# LNOccupancy.net
KiCad netlist of a schematic drawn in EAGLE
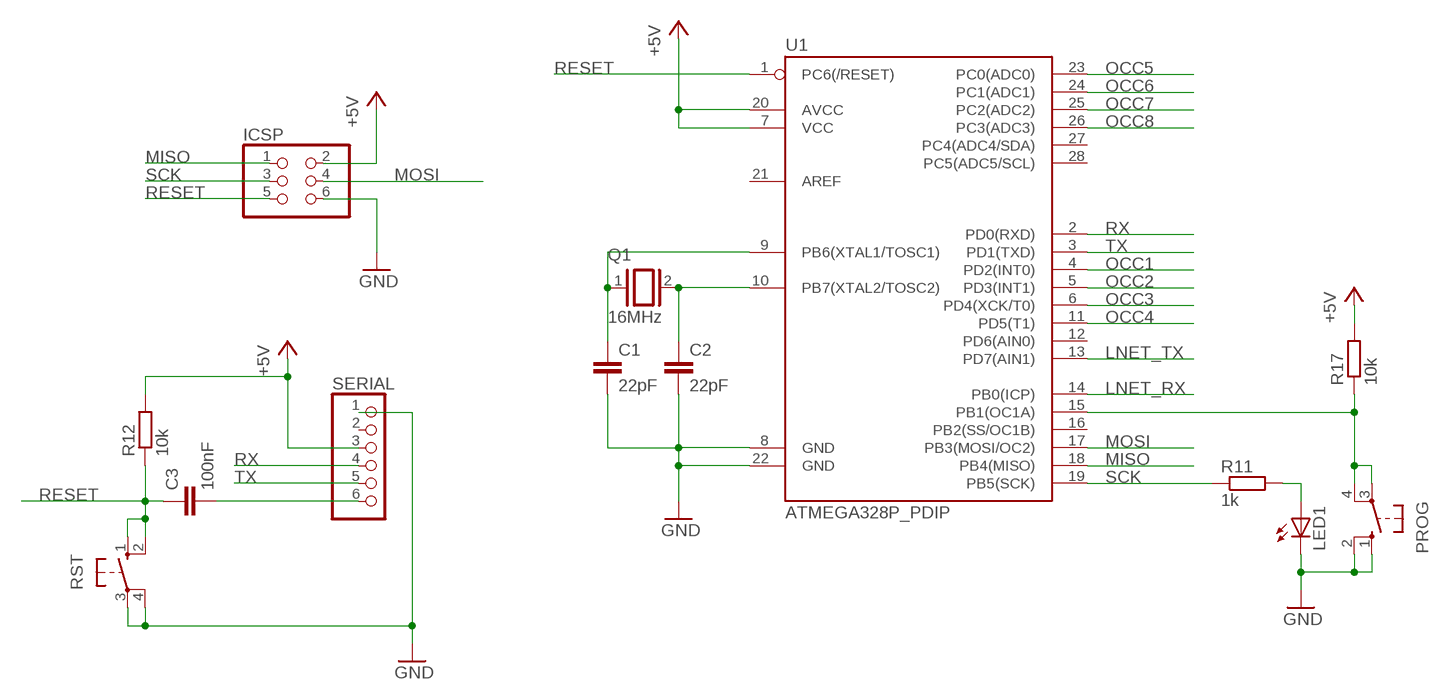
[diagram p0: schematic, sheet 1]
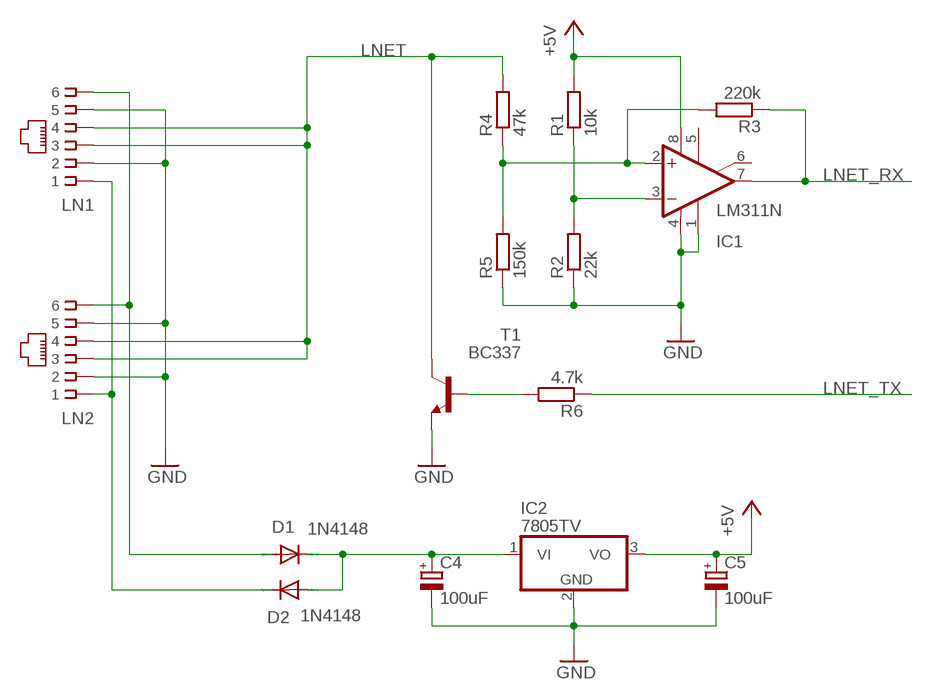
[diagram p1: schematic, sheet 2]
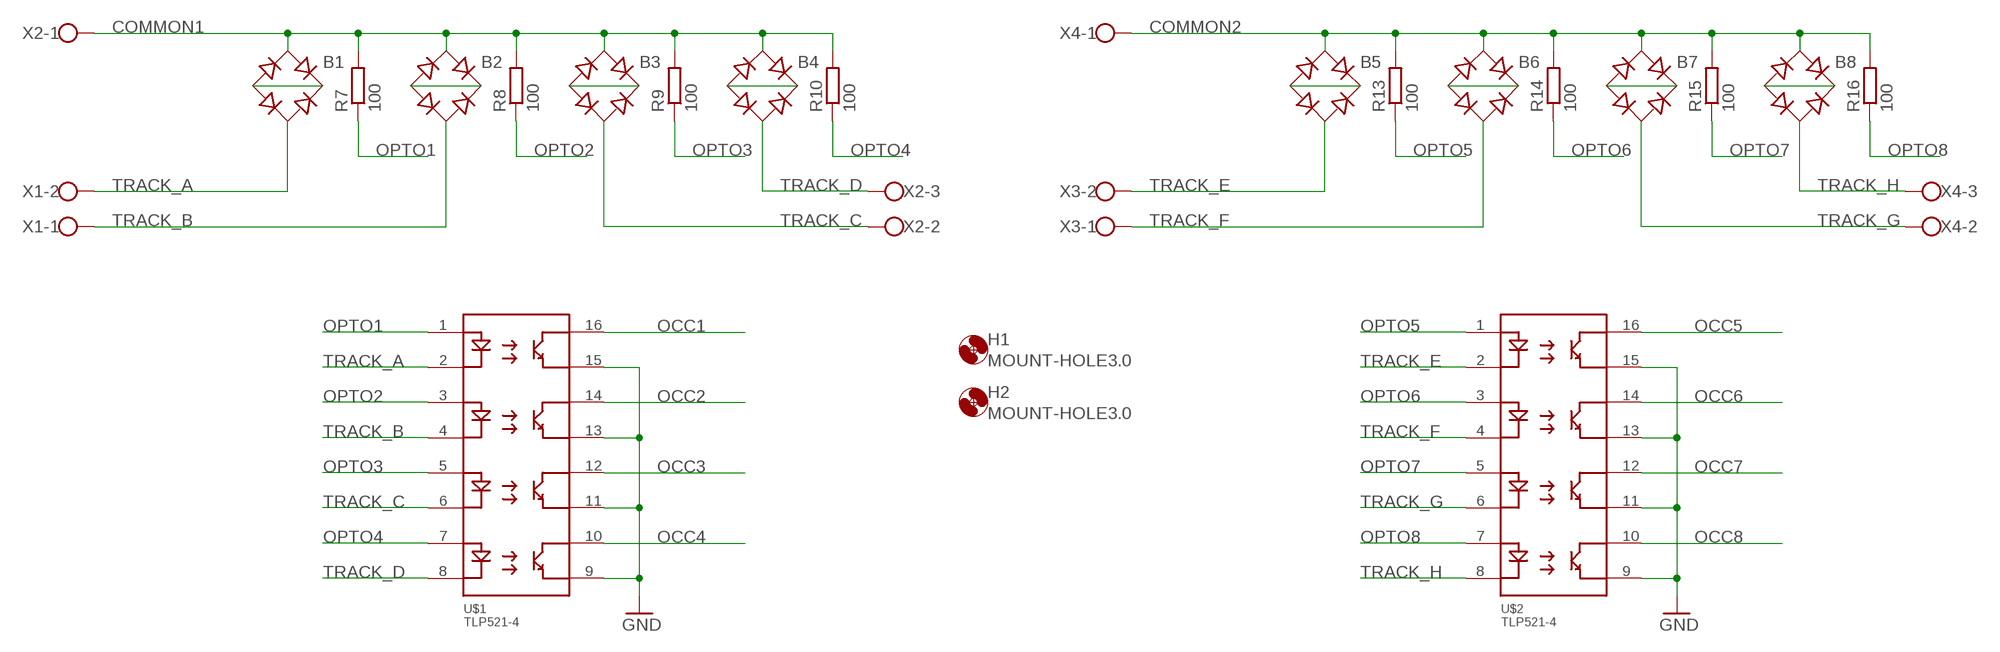
[diagram p2: schematic, sheet 3]

(export (version "E")
  (design (tool "Eeschema 10.0.6"))
  (components
    (comp (ref "C1")
      (value "22pF")
      (footprint "eagle-import:C025-025X050")
      (libsource (lib "eagle-import") (part "C-EU025-025X050"))
    )
    (comp (ref "C2")
      (value "22pF")
      (footprint "eagle-import:C025-025X050")
      (libsource (lib "eagle-import") (part "C-EU025-025X050"))
    )
    (comp (ref "C3")
      (value "100nF")
      (footprint "eagle-import:C050-025X075")
      (libsource (lib "eagle-import") (part "C-EU050-025X075"))
    )
    (comp (ref "ICSP")
      (value "PINHD-2X3")
      (footprint "eagle-import:2X03")
      (libsource (lib "eagle-import") (part "PINHD-2X3"))
    )
    (comp (ref "LED1")
      (value "LED3MM")
      (footprint "eagle-import:LED3MM")
      (libsource (lib "eagle-import") (part "LED3MM"))
    )
    (comp (ref "PROG")
      (value "10-XX")
      (footprint "eagle-import:B3F-10XX")
      (fields (field (name "MPN") "B3F-1000"))
      (libsource (lib "eagle-import") (part "10-XX"))
    )
    (comp (ref "Q1")
      (value "16MHz")
      (footprint "eagle-import:QS")
      (libsource (lib "eagle-import") (part "XTAL/S"))
    )
    (comp (ref "R11")
      (value "1k")
      (footprint "eagle-import:0207_2V")
      (libsource (lib "eagle-import") (part "R-EU_0207/2V"))
    )
    (comp (ref "R12")
      (value "10k")
      (footprint "eagle-import:0207_2V")
      (libsource (lib "eagle-import") (part "R-EU_0207/2V"))
    )
    (comp (ref "R17")
      (value "10k")
      (footprint "eagle-import:0207_2V")
      (libsource (lib "eagle-import") (part "R-EU_0207/2V"))
    )
    (comp (ref "RST")
      (value "10-XX")
      (footprint "eagle-import:B3F-10XX")
      (fields (field (name "MPN") "B3F-1000"))
      (libsource (lib "eagle-import") (part "10-XX"))
    )
    (comp (ref "SERIAL")
      (value "PINHD-1X6")
      (footprint "eagle-import:1X06")
      (libsource (lib "eagle-import") (part "PINHD-1X6"))
    )
    (comp (ref "U1")
      (value "ATMEGA328P_PDIP")
      (footprint "eagle-import:DIL28-3")
      (libsource (lib "eagle-import") (part "ATMEGA328P_PDIP"))
    )
    (comp (ref "B1")
      (value "RB1A")
      (footprint "eagle-import:RB1A")
      (libsource (lib "eagle-import") (part "RB1A"))
    )
    (comp (ref "B2")
      (value "RB1A")
      (footprint "eagle-import:RB1A")
      (libsource (lib "eagle-import") (part "RB1A"))
    )
    (comp (ref "B3")
      (value "RB1A")
      (footprint "eagle-import:RB1A")
      (libsource (lib "eagle-import") (part "RB1A"))
    )
    (comp (ref "B4")
      (value "RB1A")
      (footprint "eagle-import:RB1A")
      (libsource (lib "eagle-import") (part "RB1A"))
    )
    (comp (ref "B5")
      (value "RB1A")
      (footprint "eagle-import:RB1A")
      (libsource (lib "eagle-import") (part "RB1A"))
    )
    (comp (ref "B6")
      (value "RB1A")
      (footprint "eagle-import:RB1A")
      (libsource (lib "eagle-import") (part "RB1A"))
    )
    (comp (ref "B7")
      (value "RB1A")
      (footprint "eagle-import:RB1A")
      (libsource (lib "eagle-import") (part "RB1A"))
    )
    (comp (ref "B8")
      (value "RB1A")
      (footprint "eagle-import:RB1A")
      (libsource (lib "eagle-import") (part "RB1A"))
    )
    (comp (ref "H1")
      (value "MOUNT-HOLE3.0")
      (footprint "eagle-import:3,0")
      (libsource (lib "eagle-import") (part "MOUNT-HOLE3.0"))
    )
    (comp (ref "H2")
      (value "MOUNT-HOLE3.0")
      (footprint "eagle-import:3,0")
      (libsource (lib "eagle-import") (part "MOUNT-HOLE3.0"))
    )
    (comp (ref "R7")
      (value "100")
      (footprint "eagle-import:0207_2V")
      (libsource (lib "eagle-import") (part "R-EU_0207/2V"))
    )
    (comp (ref "R8")
      (value "100")
      (footprint "eagle-import:0207_2V")
      (libsource (lib "eagle-import") (part "R-EU_0207/2V"))
    )
    (comp (ref "R9")
      (value "100")
      (footprint "eagle-import:0207_2V")
      (libsource (lib "eagle-import") (part "R-EU_0207/2V"))
    )
    (comp (ref "R10")
      (value "100")
      (footprint "eagle-import:0207_2V")
      (libsource (lib "eagle-import") (part "R-EU_0207/2V"))
    )
    (comp (ref "R13")
      (value "100")
      (footprint "eagle-import:0207_2V")
      (libsource (lib "eagle-import") (part "R-EU_0207/2V"))
    )
    (comp (ref "R14")
      (value "100")
      (footprint "eagle-import:0207_2V")
      (libsource (lib "eagle-import") (part "R-EU_0207/2V"))
    )
    (comp (ref "R15")
      (value "100")
      (footprint "eagle-import:0207_2V")
      (libsource (lib "eagle-import") (part "R-EU_0207/2V"))
    )
    (comp (ref "R16")
      (value "100")
      (footprint "eagle-import:0207_2V")
      (libsource (lib "eagle-import") (part "R-EU_0207/2V"))
    )
    (comp (ref "U$1")
      (value "TLP521-4")
      (footprint "eagle-import:DIL16")
      (libsource (lib "eagle-import") (part "TLP521-4"))
    )
    (comp (ref "U$2")
      (value "TLP521-4")
      (footprint "eagle-import:DIL16")
      (libsource (lib "eagle-import") (part "TLP521-4"))
    )
    (comp (ref "X1")
      (value "W237-102")
      (footprint "eagle-import:W237-102")
      (fields (field (name "MPN") "237-102"))
      (libsource (lib "eagle-import") (part "W237-102"))
    )
    (comp (ref "X2")
      (value "W237-103")
      (footprint "eagle-import:W237-103")
      (fields (field (name "MPN") "237-103"))
      (libsource (lib "eagle-import") (part "W237-103"))
    )
    (comp (ref "X3")
      (value "W237-102")
      (footprint "eagle-import:W237-102")
      (fields (field (name "MPN") "237-102"))
      (libsource (lib "eagle-import") (part "W237-102"))
    )
    (comp (ref "X4")
      (value "W237-103")
      (footprint "eagle-import:W237-103")
      (fields (field (name "MPN") "237-103"))
      (libsource (lib "eagle-import") (part "W237-103"))
    )
    (comp (ref "C4")
      (value "100uF")
      (footprint "eagle-import:E2,5-6")
      (libsource (lib "eagle-import") (part "CPOL-EUE2.5-6"))
    )
    (comp (ref "C5")
      (value "100uF")
      (footprint "eagle-import:E2,5-6")
      (libsource (lib "eagle-import") (part "CPOL-EUE2.5-6"))
    )
    (comp (ref "D1")
      (value "1N4148")
      (footprint "eagle-import:DO35-10")
      (libsource (lib "eagle-import") (part "1N4148DO35-10"))
    )
    (comp (ref "D2")
      (value "1N4148")
      (footprint "eagle-import:DO35-10")
      (libsource (lib "eagle-import") (part "1N4148DO35-10"))
    )
    (comp (ref "IC1")
      (value "LM311N")
      (footprint "eagle-import:DIL08")
      (libsource (lib "eagle-import") (part "LM311N"))
    )
    (comp (ref "IC2")
      (value "7805TV")
      (footprint "eagle-import:TO220V")
      (libsource (lib "eagle-import") (part "78TV05"))
    )
    (comp (ref "LN1")
      (value "RJ11-6X")
      (footprint "eagle-import:RJ11-NO_SHIELD")
      (libsource (lib "eagle-import") (part "RJ11-6X"))
    )
    (comp (ref "LN2")
      (value "RJ11-6X")
      (footprint "eagle-import:RJ11-NO_SHIELD")
      (libsource (lib "eagle-import") (part "RJ11-6X"))
    )
    (comp (ref "R1")
      (value "10k")
      (footprint "eagle-import:0207_2V")
      (libsource (lib "eagle-import") (part "R-EU_0207/2V"))
    )
    (comp (ref "R2")
      (value "22k")
      (footprint "eagle-import:0207_2V")
      (libsource (lib "eagle-import") (part "R-EU_0207/2V"))
    )
    (comp (ref "R3")
      (value "220k")
      (footprint "eagle-import:0207_2V")
      (libsource (lib "eagle-import") (part "R-EU_0207/2V"))
    )
    (comp (ref "R4")
      (value "47k")
      (footprint "eagle-import:0207_2V")
      (libsource (lib "eagle-import") (part "R-EU_0207/2V"))
    )
    (comp (ref "R5")
      (value "150k")
      (footprint "eagle-import:0207_2V")
      (libsource (lib "eagle-import") (part "R-EU_0207/2V"))
    )
    (comp (ref "R6")
      (value "4.7k")
      (footprint "eagle-import:0207_2V")
      (libsource (lib "eagle-import") (part "R-EU_0207/2V"))
    )
    (comp (ref "T1")
      (value "BC337")
      (footprint "eagle-import:TO92")
      (libsource (lib "eagle-import") (part "BC337"))
    )
  )
  (nets
    (net (code "1") (name "+5V") (class "Default")
      (node (ref "C5") (pin "+") (pinfunction "+_+") (pintype "passive"))
      (node (ref "IC1") (pin "8") (pinfunction "V+_8") (pintype "power_in"))
      (node (ref "IC2") (pin "3") (pinfunction "VO_3") (pintype "passive"))
      (node (ref "ICSP") (pin "2") (pinfunction "2_2") (pintype "passive"))
      (node (ref "R1") (pin "2") (pinfunction "2_2") (pintype "passive"))
      (node (ref "R12") (pin "2") (pinfunction "2_2") (pintype "passive"))
      (node (ref "R17") (pin "2") (pinfunction "2_2") (pintype "passive"))
      (node (ref "SERIAL") (pin "3") (pinfunction "3_3") (pintype "passive"))
      (node (ref "U1") (pin "20") (pinfunction "AVCC_20") (pintype "bidirectional"))
      (node (ref "U1") (pin "7") (pinfunction "VCC_7") (pintype "bidirectional"))
    )
    (net (code "2") (name "COMMON1") (class "Default")
      (node (ref "B1") (pin "AC1") (pinfunction "AC1_AC1") (pintype "passive"))
      (node (ref "B2") (pin "AC1") (pinfunction "AC1_AC1") (pintype "passive"))
      (node (ref "B3") (pin "AC1") (pinfunction "AC1_AC1") (pintype "passive"))
      (node (ref "B4") (pin "AC1") (pinfunction "AC1_AC1") (pintype "passive"))
      (node (ref "R10") (pin "2") (pinfunction "2_2") (pintype "passive"))
      (node (ref "R7") (pin "2") (pinfunction "2_2") (pintype "passive"))
      (node (ref "R8") (pin "2") (pinfunction "2_2") (pintype "passive"))
      (node (ref "R9") (pin "2") (pinfunction "2_2") (pintype "passive"))
      (node (ref "X2") (pin "1") (pinfunction "KL_1") (pintype "passive"))
    )
    (net (code "3") (name "COMMON2") (class "Default")
      (node (ref "B5") (pin "AC1") (pinfunction "AC1_AC1") (pintype "passive"))
      (node (ref "B6") (pin "AC1") (pinfunction "AC1_AC1") (pintype "passive"))
      (node (ref "B7") (pin "AC1") (pinfunction "AC1_AC1") (pintype "passive"))
      (node (ref "B8") (pin "AC1") (pinfunction "AC1_AC1") (pintype "passive"))
      (node (ref "R13") (pin "2") (pinfunction "2_2") (pintype "passive"))
      (node (ref "R14") (pin "2") (pinfunction "2_2") (pintype "passive"))
      (node (ref "R15") (pin "2") (pinfunction "2_2") (pintype "passive"))
      (node (ref "R16") (pin "2") (pinfunction "2_2") (pintype "passive"))
      (node (ref "X4") (pin "1") (pinfunction "KL_1") (pintype "passive"))
    )
    (net (code "4") (name "GND") (class "Default")
      (node (ref "C1") (pin "2") (pinfunction "2_2") (pintype "passive"))
      (node (ref "C2") (pin "2") (pinfunction "2_2") (pintype "passive"))
      (node (ref "C4") (pin "-") (pinfunction "-_-") (pintype "passive"))
      (node (ref "C5") (pin "-") (pinfunction "-_-") (pintype "passive"))
      (node (ref "IC1") (pin "1") (pinfunction "GND_1") (pintype "passive"))
      (node (ref "IC1") (pin "4") (pinfunction "V-_4") (pintype "power_in"))
      (node (ref "IC2") (pin "2") (pinfunction "GND_2") (pintype "passive"))
      (node (ref "ICSP") (pin "6") (pinfunction "6_6") (pintype "passive"))
      (node (ref "LED1") (pin "K") (pinfunction "C_K") (pintype "passive"))
      (node (ref "LN1") (pin "2") (pinfunction "2_2") (pintype "passive"))
      (node (ref "LN1") (pin "5") (pinfunction "5_5") (pintype "passive"))
      (node (ref "LN2") (pin "2") (pinfunction "2_2") (pintype "passive"))
      (node (ref "LN2") (pin "5") (pinfunction "5_5") (pintype "passive"))
      (node (ref "PROG") (pin "1") (pinfunction "S_1") (pintype "passive"))
      (node (ref "PROG") (pin "2") (pinfunction "S1_2") (pintype "passive"))
      (node (ref "R2") (pin "1") (pinfunction "1_1") (pintype "passive"))
      (node (ref "R5") (pin "1") (pinfunction "1_1") (pintype "passive"))
      (node (ref "RST") (pin "3") (pinfunction "P_3") (pintype "passive"))
      (node (ref "RST") (pin "4") (pinfunction "P1_4") (pintype "passive"))
      (node (ref "SERIAL") (pin "1") (pinfunction "1_1") (pintype "passive"))
      (node (ref "T1") (pin "1") (pinfunction "E_1") (pintype "passive"))
      (node (ref "U$1") (pin "11") (pinfunction "P$11_11") (pintype "bidirectional"))
      (node (ref "U$1") (pin "13") (pinfunction "P$13_13") (pintype "bidirectional"))
      (node (ref "U$1") (pin "15") (pinfunction "P$15_15") (pintype "bidirectional"))
      (node (ref "U$1") (pin "9") (pinfunction "P$9_9") (pintype "bidirectional"))
      (node (ref "U$2") (pin "11") (pinfunction "P$11_11") (pintype "bidirectional"))
      (node (ref "U$2") (pin "13") (pinfunction "P$13_13") (pintype "bidirectional"))
      (node (ref "U$2") (pin "15") (pinfunction "P$15_15") (pintype "bidirectional"))
      (node (ref "U$2") (pin "9") (pinfunction "P$9_9") (pintype "bidirectional"))
      (node (ref "U1") (pin "22") (pinfunction "GND_22") (pintype "bidirectional"))
      (node (ref "U1") (pin "8") (pinfunction "GND_8") (pintype "bidirectional"))
    )
    (net (code "5") (name "LNET") (class "Default")
      (node (ref "LN1") (pin "3") (pinfunction "3_3") (pintype "passive"))
      (node (ref "LN1") (pin "4") (pinfunction "4_4") (pintype "passive"))
      (node (ref "LN2") (pin "3") (pinfunction "3_3") (pintype "passive"))
      (node (ref "LN2") (pin "4") (pinfunction "4_4") (pintype "passive"))
      (node (ref "R4") (pin "2") (pinfunction "2_2") (pintype "passive"))
      (node (ref "T1") (pin "3") (pinfunction "C_3") (pintype "passive"))
    )
    (net (code "6") (name "LNET_RX") (class "Default")
      (node (ref "IC1") (pin "7") (pinfunction "OUT_7") (pintype "output"))
      (node (ref "R3") (pin "1") (pinfunction "1_1") (pintype "passive"))
      (node (ref "U1") (pin "14") (pinfunction "PB0(ICP)_14") (pintype "bidirectional"))
    )
    (net (code "7") (name "LNET_TX") (class "Default")
      (node (ref "R6") (pin "1") (pinfunction "1_1") (pintype "passive"))
      (node (ref "U1") (pin "13") (pinfunction "PD7(AIN1)_13") (pintype "bidirectional"))
    )
    (net (code "8") (name "MISO") (class "Default")
      (node (ref "ICSP") (pin "1") (pinfunction "1_1") (pintype "passive"))
      (node (ref "U1") (pin "18") (pinfunction "PB4(MISO)_18") (pintype "bidirectional"))
    )
    (net (code "9") (name "MOSI") (class "Default")
      (node (ref "ICSP") (pin "4") (pinfunction "4_4") (pintype "passive"))
      (node (ref "U1") (pin "17") (pinfunction "PB3(MOSI/OC2)_17") (pintype "bidirectional"))
    )
    (net (code "10") (name "Net-(B1-Pad+)") (class "Default")
      (node (ref "B1") (pin "+") (pinfunction "+_+") (pintype "passive"))
      (node (ref "B1") (pin "-") (pinfunction "-_-") (pintype "passive"))
    )
    (net (code "11") (name "Net-(B2-Pad+)") (class "Default")
      (node (ref "B2") (pin "+") (pinfunction "+_+") (pintype "passive"))
      (node (ref "B2") (pin "-") (pinfunction "-_-") (pintype "passive"))
    )
    (net (code "12") (name "Net-(B3-Pad+)") (class "Default")
      (node (ref "B3") (pin "+") (pinfunction "+_+") (pintype "passive"))
      (node (ref "B3") (pin "-") (pinfunction "-_-") (pintype "passive"))
    )
    (net (code "13") (name "Net-(B4-Pad+)") (class "Default")
      (node (ref "B4") (pin "+") (pinfunction "+_+") (pintype "passive"))
      (node (ref "B4") (pin "-") (pinfunction "-_-") (pintype "passive"))
    )
    (net (code "14") (name "Net-(B5-Pad+)") (class "Default")
      (node (ref "B5") (pin "+") (pinfunction "+_+") (pintype "passive"))
      (node (ref "B5") (pin "-") (pinfunction "-_-") (pintype "passive"))
    )
    (net (code "15") (name "Net-(B6-Pad+)") (class "Default")
      (node (ref "B6") (pin "+") (pinfunction "+_+") (pintype "passive"))
      (node (ref "B6") (pin "-") (pinfunction "-_-") (pintype "passive"))
    )
    (net (code "16") (name "Net-(B7-Pad+)") (class "Default")
      (node (ref "B7") (pin "+") (pinfunction "+_+") (pintype "passive"))
      (node (ref "B7") (pin "-") (pinfunction "-_-") (pintype "passive"))
    )
    (net (code "17") (name "Net-(B8-Pad+)") (class "Default")
      (node (ref "B8") (pin "+") (pinfunction "+_+") (pintype "passive"))
      (node (ref "B8") (pin "-") (pinfunction "-_-") (pintype "passive"))
    )
    (net (code "18") (name "Net-(C3-Pad2)") (class "Default")
      (node (ref "C3") (pin "2") (pinfunction "2_2") (pintype "passive"))
      (node (ref "SERIAL") (pin "6") (pinfunction "6_6") (pintype "passive"))
    )
    (net (code "19") (name "Net-(D1-PadA)") (class "Default")
      (node (ref "D1") (pin "A") (pinfunction "A_A") (pintype "passive"))
      (node (ref "LN1") (pin "6") (pinfunction "6_6") (pintype "passive"))
      (node (ref "LN2") (pin "6") (pinfunction "6_6") (pintype "passive"))
    )
    (net (code "20") (name "Net-(D2-PadC)") (class "Default")
      (node (ref "D2") (pin "C") (pinfunction "C_C") (pintype "passive"))
      (node (ref "LN1") (pin "1") (pinfunction "1_1") (pintype "passive"))
      (node (ref "LN2") (pin "1") (pinfunction "1_1") (pintype "passive"))
    )
    (net (code "21") (name "Net-(IC1-+IN)") (class "Default")
      (node (ref "IC1") (pin "2") (pinfunction "+IN_2") (pintype "input"))
      (node (ref "R3") (pin "2") (pinfunction "2_2") (pintype "passive"))
      (node (ref "R4") (pin "1") (pinfunction "1_1") (pintype "passive"))
      (node (ref "R5") (pin "2") (pinfunction "2_2") (pintype "passive"))
    )
    (net (code "22") (name "Net-(IC1--IN)") (class "Default")
      (node (ref "IC1") (pin "3") (pinfunction "-IN_3") (pintype "input"))
      (node (ref "R1") (pin "1") (pinfunction "1_1") (pintype "passive"))
      (node (ref "R2") (pin "2") (pinfunction "2_2") (pintype "passive"))
    )
    (net (code "23") (name "Net-(IC2-VI)") (class "Default")
      (node (ref "C4") (pin "+") (pinfunction "+_+") (pintype "passive"))
      (node (ref "D1") (pin "C") (pinfunction "C_C") (pintype "passive"))
      (node (ref "D2") (pin "A") (pinfunction "A_A") (pintype "passive"))
      (node (ref "IC2") (pin "1") (pinfunction "VI_1") (pintype "input"))
    )
    (net (code "24") (name "Net-(LED1-PadA)") (class "Default")
      (node (ref "LED1") (pin "A") (pinfunction "A_A") (pintype "passive"))
      (node (ref "R11") (pin "2") (pinfunction "2_2") (pintype "passive"))
    )
    (net (code "25") (name "Net-(PROG-P)") (class "Default")
      (node (ref "PROG") (pin "3") (pinfunction "P_3") (pintype "passive"))
      (node (ref "PROG") (pin "4") (pinfunction "P1_4") (pintype "passive"))
      (node (ref "R17") (pin "1") (pinfunction "1_1") (pintype "passive"))
      (node (ref "U1") (pin "15") (pinfunction "PB1(OC1A)_15") (pintype "bidirectional"))
    )
    (net (code "26") (name "Net-(T1-B)") (class "Default")
      (node (ref "R6") (pin "2") (pinfunction "2_2") (pintype "passive"))
      (node (ref "T1") (pin "2") (pinfunction "B_2") (pintype "passive"))
    )
    (net (code "27") (name "Net-(U1-PB6(XTAL1{slash}TOSC1))") (class "Default")
      (node (ref "C1") (pin "1") (pinfunction "1_1") (pintype "passive"))
      (node (ref "Q1") (pin "1") (pinfunction "1_1") (pintype "passive"))
      (node (ref "U1") (pin "9") (pinfunction "PB6(XTAL1/TOSC1)_9") (pintype "bidirectional"))
    )
    (net (code "28") (name "Net-(U1-PB7(XTAL2{slash}TOSC2))") (class "Default")
      (node (ref "C2") (pin "1") (pinfunction "1_1") (pintype "passive"))
      (node (ref "Q1") (pin "2") (pinfunction "2_2") (pintype "passive"))
      (node (ref "U1") (pin "10") (pinfunction "PB7(XTAL2/TOSC2)_10") (pintype "bidirectional"))
    )
    (net (code "29") (name "OCC1") (class "Default")
      (node (ref "U$1") (pin "16") (pinfunction "P$16_16") (pintype "bidirectional"))
      (node (ref "U1") (pin "4") (pinfunction "PD2(INT0)_4") (pintype "bidirectional"))
    )
    (net (code "30") (name "OCC2") (class "Default")
      (node (ref "U$1") (pin "14") (pinfunction "P$14_14") (pintype "bidirectional"))
      (node (ref "U1") (pin "5") (pinfunction "PD3(INT1)_5") (pintype "bidirectional"))
    )
    (net (code "31") (name "OCC3") (class "Default")
      (node (ref "U$1") (pin "12") (pinfunction "P$12_12") (pintype "bidirectional"))
      (node (ref "U1") (pin "6") (pinfunction "PD4(XCK/T0)_6") (pintype "bidirectional"))
    )
    (net (code "32") (name "OCC4") (class "Default")
      (node (ref "U$1") (pin "10") (pinfunction "P$10_10") (pintype "bidirectional"))
      (node (ref "U1") (pin "11") (pinfunction "PD5(T1)_11") (pintype "bidirectional"))
    )
    (net (code "33") (name "OCC5") (class "Default")
      (node (ref "U$2") (pin "16") (pinfunction "P$16_16") (pintype "bidirectional"))
      (node (ref "U1") (pin "23") (pinfunction "PC0(ADC0)_23") (pintype "bidirectional"))
    )
    (net (code "34") (name "OCC6") (class "Default")
      (node (ref "U$2") (pin "14") (pinfunction "P$14_14") (pintype "bidirectional"))
      (node (ref "U1") (pin "24") (pinfunction "PC1(ADC1)_24") (pintype "bidirectional"))
    )
    (net (code "35") (name "OCC7") (class "Default")
      (node (ref "U$2") (pin "12") (pinfunction "P$12_12") (pintype "bidirectional"))
      (node (ref "U1") (pin "25") (pinfunction "PC2(ADC2)_25") (pintype "bidirectional"))
    )
    (net (code "36") (name "OCC8") (class "Default")
      (node (ref "U$2") (pin "10") (pinfunction "P$10_10") (pintype "bidirectional"))
      (node (ref "U1") (pin "26") (pinfunction "PC3(ADC3)_26") (pintype "bidirectional"))
    )
    (net (code "37") (name "OPTO1") (class "Default")
      (node (ref "R7") (pin "1") (pinfunction "1_1") (pintype "passive"))
      (node (ref "U$1") (pin "1") (pinfunction "P$1_1") (pintype "bidirectional"))
    )
    (net (code "38") (name "OPTO2") (class "Default")
      (node (ref "R8") (pin "1") (pinfunction "1_1") (pintype "passive"))
      (node (ref "U$1") (pin "3") (pinfunction "P$3_3") (pintype "bidirectional"))
    )
    (net (code "39") (name "OPTO3") (class "Default")
      (node (ref "R9") (pin "1") (pinfunction "1_1") (pintype "passive"))
      (node (ref "U$1") (pin "5") (pinfunction "P$5_5") (pintype "bidirectional"))
    )
    (net (code "40") (name "OPTO4") (class "Default")
      (node (ref "R10") (pin "1") (pinfunction "1_1") (pintype "passive"))
      (node (ref "U$1") (pin "7") (pinfunction "P$7_7") (pintype "bidirectional"))
    )
    (net (code "41") (name "OPTO5") (class "Default")
      (node (ref "R13") (pin "1") (pinfunction "1_1") (pintype "passive"))
      (node (ref "U$2") (pin "1") (pinfunction "P$1_1") (pintype "bidirectional"))
    )
    (net (code "42") (name "OPTO6") (class "Default")
      (node (ref "R14") (pin "1") (pinfunction "1_1") (pintype "passive"))
      (node (ref "U$2") (pin "3") (pinfunction "P$3_3") (pintype "bidirectional"))
    )
    (net (code "43") (name "OPTO7") (class "Default")
      (node (ref "R15") (pin "1") (pinfunction "1_1") (pintype "passive"))
      (node (ref "U$2") (pin "5") (pinfunction "P$5_5") (pintype "bidirectional"))
    )
    (net (code "44") (name "OPTO8") (class "Default")
      (node (ref "R16") (pin "1") (pinfunction "1_1") (pintype "passive"))
      (node (ref "U$2") (pin "7") (pinfunction "P$7_7") (pintype "bidirectional"))
    )
    (net (code "45") (name "RESET") (class "Default")
      (node (ref "C3") (pin "1") (pinfunction "1_1") (pintype "passive"))
      (node (ref "ICSP") (pin "5") (pinfunction "5_5") (pintype "passive"))
      (node (ref "R12") (pin "1") (pinfunction "1_1") (pintype "passive"))
      (node (ref "RST") (pin "1") (pinfunction "S_1") (pintype "passive"))
      (node (ref "RST") (pin "2") (pinfunction "S1_2") (pintype "passive"))
      (node (ref "U1") (pin "1") (pinfunction "PC6(/RESET)_1") (pintype "bidirectional"))
    )
    (net (code "46") (name "RX") (class "Default")
      (node (ref "SERIAL") (pin "4") (pinfunction "4_4") (pintype "passive"))
      (node (ref "U1") (pin "2") (pinfunction "PD0(RXD)_2") (pintype "bidirectional"))
    )
    (net (code "47") (name "SCK") (class "Default")
      (node (ref "ICSP") (pin "3") (pinfunction "3_3") (pintype "passive"))
      (node (ref "R11") (pin "1") (pinfunction "1_1") (pintype "passive"))
      (node (ref "U1") (pin "19") (pinfunction "PB5(SCK)_19") (pintype "bidirectional"))
    )
    (net (code "48") (name "TRACK_A") (class "Default")
      (node (ref "B1") (pin "AC2") (pinfunction "AC2_AC2") (pintype "passive"))
      (node (ref "U$1") (pin "2") (pinfunction "P$2_2") (pintype "bidirectional"))
      (node (ref "X1") (pin "2") (pinfunction "KL_2") (pintype "passive"))
    )
    (net (code "49") (name "TRACK_B") (class "Default")
      (node (ref "B2") (pin "AC2") (pinfunction "AC2_AC2") (pintype "passive"))
      (node (ref "U$1") (pin "4") (pinfunction "P$4_4") (pintype "bidirectional"))
      (node (ref "X1") (pin "1") (pinfunction "KL_1") (pintype "passive"))
    )
    (net (code "50") (name "TRACK_C") (class "Default")
      (node (ref "B3") (pin "AC2") (pinfunction "AC2_AC2") (pintype "passive"))
      (node (ref "U$1") (pin "6") (pinfunction "P$6_6") (pintype "bidirectional"))
      (node (ref "X2") (pin "2") (pinfunction "KL_2") (pintype "passive"))
    )
    (net (code "51") (name "TRACK_D") (class "Default")
      (node (ref "B4") (pin "AC2") (pinfunction "AC2_AC2") (pintype "passive"))
      (node (ref "U$1") (pin "8") (pinfunction "P$8_8") (pintype "bidirectional"))
      (node (ref "X2") (pin "3") (pinfunction "KL_3") (pintype "passive"))
    )
    (net (code "52") (name "TRACK_E") (class "Default")
      (node (ref "B5") (pin "AC2") (pinfunction "AC2_AC2") (pintype "passive"))
      (node (ref "U$2") (pin "2") (pinfunction "P$2_2") (pintype "bidirectional"))
      (node (ref "X3") (pin "2") (pinfunction "KL_2") (pintype "passive"))
    )
    (net (code "53") (name "TRACK_F") (class "Default")
      (node (ref "B6") (pin "AC2") (pinfunction "AC2_AC2") (pintype "passive"))
      (node (ref "U$2") (pin "4") (pinfunction "P$4_4") (pintype "bidirectional"))
      (node (ref "X3") (pin "1") (pinfunction "KL_1") (pintype "passive"))
    )
    (net (code "54") (name "TRACK_G") (class "Default")
      (node (ref "B7") (pin "AC2") (pinfunction "AC2_AC2") (pintype "passive"))
      (node (ref "U$2") (pin "6") (pinfunction "P$6_6") (pintype "bidirectional"))
      (node (ref "X4") (pin "2") (pinfunction "KL_2") (pintype "passive"))
    )
    (net (code "55") (name "TRACK_H") (class "Default")
      (node (ref "B8") (pin "AC2") (pinfunction "AC2_AC2") (pintype "passive"))
      (node (ref "U$2") (pin "8") (pinfunction "P$8_8") (pintype "bidirectional"))
      (node (ref "X4") (pin "3") (pinfunction "KL_3") (pintype "passive"))
    )
    (net (code "56") (name "TX") (class "Default")
      (node (ref "SERIAL") (pin "5") (pinfunction "5_5") (pintype "passive"))
      (node (ref "U1") (pin "3") (pinfunction "PD1(TXD)_3") (pintype "bidirectional"))
    )
    (net (code "57") (name "unconnected-(IC1-ON-Pad5)") (class "Default")
      (node (ref "IC1") (pin "5") (pinfunction "ON_5") (pintype "passive"))
    )
    (net (code "58") (name "unconnected-(IC1-ON{slash}STR-Pad6)") (class "Default")
      (node (ref "IC1") (pin "6") (pinfunction "ON/STR_6") (pintype "passive"))
    )
    (net (code "59") (name "unconnected-(SERIAL-Pad2)") (class "Default")
      (node (ref "SERIAL") (pin "2") (pinfunction "2_2") (pintype "passive"))
    )
    (net (code "60") (name "unconnected-(U1-AREF-Pad21)") (class "Default")
      (node (ref "U1") (pin "21") (pinfunction "AREF_21") (pintype "bidirectional"))
    )
    (net (code "61") (name "unconnected-(U1-PB2(SS{slash}OC1B)-Pad16)") (class "Default")
      (node (ref "U1") (pin "16") (pinfunction "PB2(SS/OC1B)_16") (pintype "bidirectional"))
    )
    (net (code "62") (name "unconnected-(U1-PC4(ADC4{slash}SDA)-Pad27)") (class "Default")
      (node (ref "U1") (pin "27") (pinfunction "PC4(ADC4/SDA)_27") (pintype "bidirectional"))
    )
    (net (code "63") (name "unconnected-(U1-PC5(ADC5{slash}SCL)-Pad28)") (class "Default")
      (node (ref "U1") (pin "28") (pinfunction "PC5(ADC5/SCL)_28") (pintype "bidirectional"))
    )
    (net (code "64") (name "unconnected-(U1-PD6(AIN0)-Pad12)") (class "Default")
      (node (ref "U1") (pin "12") (pinfunction "PD6(AIN0)_12") (pintype "bidirectional"))
    )
  )
)
